# COMPLETE_ArduinoShield_8x8DM.net
KiCad netlist of a schematic drawn in EAGLE
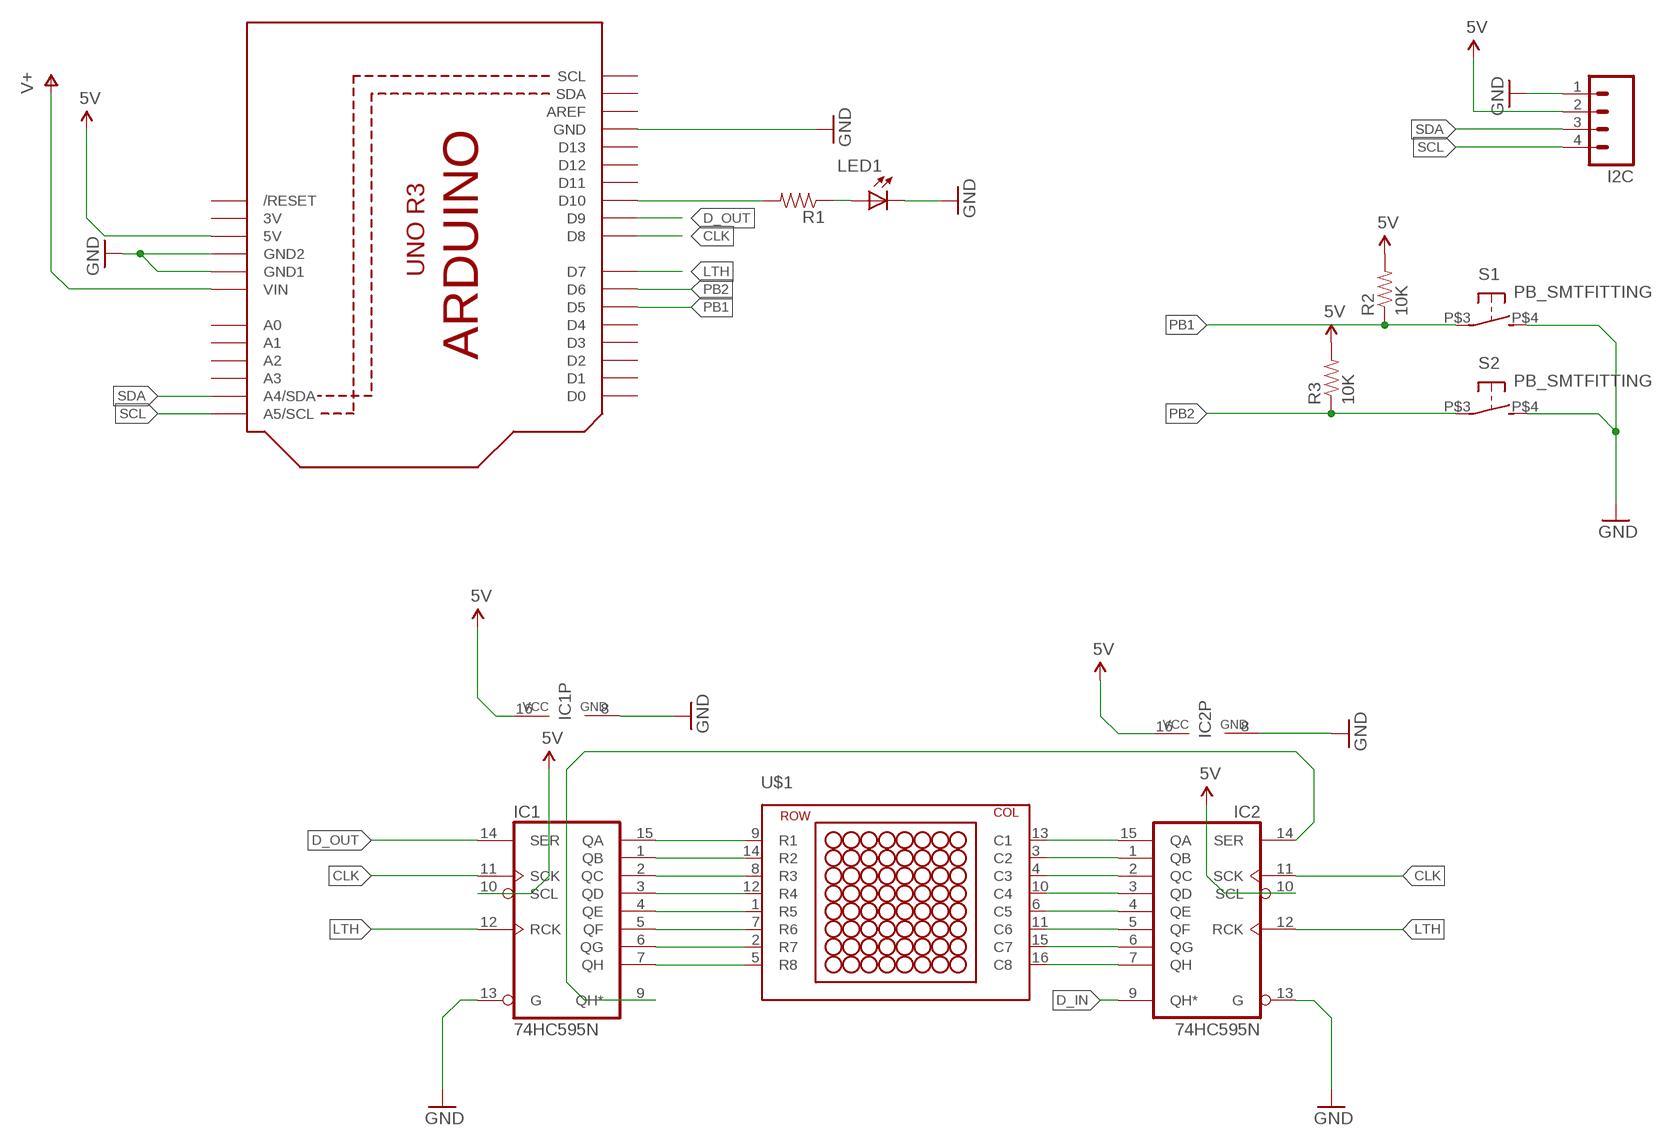
[diagram p0: schematic, sheet 1]

(export (version "E")
  (design (tool "Eeschema 10.0.6"))
  (components
    (comp (ref "I2C")
      (value "M04PTH")
      (footprint "eagle-import:1X04")
      (libsource (lib "eagle-import") (part "M04PTH"))
    )
    (comp (ref "IC1")
      (value "74HC595N")
      (footprint "eagle-import:DIL16")
      (libsource (lib "eagle-import") (part "74595NHC"))
    )
    (comp (ref "IC2")
      (value "74HC595N")
      (footprint "eagle-import:DIL16")
      (libsource (lib "eagle-import") (part "74595NHC"))
    )
    (comp (ref "LED1")
      (value "LED/0805")
      (footprint "eagle-import:CHIP-LED0805")
      (libsource (lib "eagle-import") (part "LED/0805"))
    )
    (comp (ref "R1")
      (value "RESISTOR0805-RES")
      (footprint "eagle-import:0805")
      (libsource (lib "eagle-import") (part "RESISTOR0805-RES"))
    )
    (comp (ref "R2")
      (value "10K")
      (footprint "eagle-import:0805")
      (libsource (lib "eagle-import") (part "RESISTOR0805-RES"))
    )
    (comp (ref "R3")
      (value "10K")
      (footprint "eagle-import:0805")
      (libsource (lib "eagle-import") (part "RESISTOR0805-RES"))
    )
    (comp (ref "S1")
      (value "PB_SMTFITTING")
      (footprint "eagle-import:PB_SMT_TIGHT")
      (libsource (lib "eagle-import") (part "PB_SMTFITTING"))
    )
    (comp (ref "S2")
      (value "PB_SMTFITTING")
      (footprint "eagle-import:PB_SMT_TIGHT")
      (libsource (lib "eagle-import") (part "PB_SMTFITTING"))
    )
    (comp (ref "U$1")
      (value "8X8DM_2088AS")
      (footprint "eagle-import:8X8DM_2088AS")
      (libsource (lib "eagle-import") (part "8X8DM_2088AS"))
    )
    (comp (ref "U1")
      (value "ARDUINOR3-NOIOREF-NOTEXT")
      (footprint "eagle-import:ARDUINOR3-NOTEXT-NOIOREF")
      (libsource (lib "eagle-import") (part "ARDUINOR3-NOIOREF-NOTEXT"))
    )
  )
  (nets
    (net (code "1") (name "/3V") (class "Default")
      (node (ref "U1") (pin "3V") (pinfunction "3V_3V") (pintype "power_in"))
    )
    (net (code "2") (name "5V") (class "Default")
      (node (ref "I2C") (pin "2") (pinfunction "2_2") (pintype "passive"))
      (node (ref "IC1") (pin "10") (pinfunction "SCL_10") (pintype "input"))
      (node (ref "IC1") (pin "16") (pinfunction "VCC_16") (pintype "power_in"))
      (node (ref "IC2") (pin "10") (pinfunction "SCL_10") (pintype "input"))
      (node (ref "IC2") (pin "16") (pinfunction "VCC_16") (pintype "power_in"))
      (node (ref "R2") (pin "2") (pinfunction "2_2") (pintype "passive"))
      (node (ref "R3") (pin "2") (pinfunction "2_2") (pintype "passive"))
      (node (ref "U1") (pin "5V") (pinfunction "5V_5V") (pintype "power_in"))
    )
    (net (code "3") (name "CLK") (class "Default")
      (node (ref "IC1") (pin "11") (pinfunction "SCK_11") (pintype "input"))
      (node (ref "IC2") (pin "11") (pinfunction "SCK_11") (pintype "input"))
      (node (ref "U1") (pin "D8") (pinfunction "D8_D8") (pintype "bidirectional"))
    )
    (net (code "4") (name "D_IN") (class "Default")
      (node (ref "IC2") (pin "9") (pinfunction "QH*_9") (pintype "tri_state"))
    )
    (net (code "5") (name "D_OUT") (class "Default")
      (node (ref "IC1") (pin "14") (pinfunction "SER_14") (pintype "input"))
      (node (ref "U1") (pin "D9") (pinfunction "D9_D9") (pintype "bidirectional"))
    )
    (net (code "6") (name "GND") (class "Default")
      (node (ref "I2C") (pin "1") (pinfunction "1_1") (pintype "passive"))
      (node (ref "IC1") (pin "13") (pinfunction "G_13") (pintype "input"))
      (node (ref "IC1") (pin "8") (pinfunction "GND_8") (pintype "power_in"))
      (node (ref "IC2") (pin "13") (pinfunction "G_13") (pintype "input"))
      (node (ref "IC2") (pin "8") (pinfunction "GND_8") (pintype "power_in"))
      (node (ref "LED1") (pin "C") (pinfunction "C_C") (pintype "passive"))
      (node (ref "S1") (pin "P$4") (pinfunction "2_P$4") (pintype "passive"))
      (node (ref "S2") (pin "P$4") (pinfunction "2_P$4") (pintype "passive"))
      (node (ref "U1") (pin "GND") (pinfunction "GND_GND") (pintype "power_in"))
      (node (ref "U1") (pin "GND1") (pinfunction "GND1_GND1") (pintype "power_in"))
      (node (ref "U1") (pin "GND2") (pinfunction "GND2_GND2") (pintype "power_in"))
    )
    (net (code "7") (name "LTH") (class "Default")
      (node (ref "IC1") (pin "12") (pinfunction "RCK_12") (pintype "input"))
      (node (ref "IC2") (pin "12") (pinfunction "RCK_12") (pintype "input"))
      (node (ref "U1") (pin "D7") (pinfunction "D7_D7") (pintype "bidirectional"))
    )
    (net (code "8") (name "Net-(IC1A-QA)") (class "Default")
      (node (ref "IC1") (pin "15") (pinfunction "QA_15") (pintype "tri_state"))
      (node (ref "U$1") (pin "9") (pinfunction "R1_9") (pintype "bidirectional"))
    )
    (net (code "9") (name "Net-(IC1A-QB)") (class "Default")
      (node (ref "IC1") (pin "1") (pinfunction "QB_1") (pintype "tri_state"))
      (node (ref "U$1") (pin "14") (pinfunction "R2_14") (pintype "bidirectional"))
    )
    (net (code "10") (name "Net-(IC1A-QC)") (class "Default")
      (node (ref "IC1") (pin "2") (pinfunction "QC_2") (pintype "tri_state"))
      (node (ref "U$1") (pin "8") (pinfunction "R3_8") (pintype "bidirectional"))
    )
    (net (code "11") (name "Net-(IC1A-QD)") (class "Default")
      (node (ref "IC1") (pin "3") (pinfunction "QD_3") (pintype "tri_state"))
      (node (ref "U$1") (pin "12") (pinfunction "R4_12") (pintype "bidirectional"))
    )
    (net (code "12") (name "Net-(IC1A-QE)") (class "Default")
      (node (ref "IC1") (pin "4") (pinfunction "QE_4") (pintype "tri_state"))
      (node (ref "U$1") (pin "1") (pinfunction "R5_1") (pintype "bidirectional"))
    )
    (net (code "13") (name "Net-(IC1A-QF)") (class "Default")
      (node (ref "IC1") (pin "5") (pinfunction "QF_5") (pintype "tri_state"))
      (node (ref "U$1") (pin "7") (pinfunction "R6_7") (pintype "bidirectional"))
    )
    (net (code "14") (name "Net-(IC1A-QG)") (class "Default")
      (node (ref "IC1") (pin "6") (pinfunction "QG_6") (pintype "tri_state"))
      (node (ref "U$1") (pin "2") (pinfunction "R7_2") (pintype "bidirectional"))
    )
    (net (code "15") (name "Net-(IC1A-QH)") (class "Default")
      (node (ref "IC1") (pin "7") (pinfunction "QH_7") (pintype "tri_state"))
      (node (ref "U$1") (pin "5") (pinfunction "R8_5") (pintype "bidirectional"))
    )
    (net (code "16") (name "Net-(IC1A-QH*)") (class "Default")
      (node (ref "IC1") (pin "9") (pinfunction "QH*_9") (pintype "tri_state"))
      (node (ref "IC2") (pin "14") (pinfunction "SER_14") (pintype "input"))
    )
    (net (code "17") (name "Net-(IC2A-QA)") (class "Default")
      (node (ref "IC2") (pin "15") (pinfunction "QA_15") (pintype "tri_state"))
      (node (ref "U$1") (pin "13") (pinfunction "C1_13") (pintype "bidirectional"))
    )
    (net (code "18") (name "Net-(IC2A-QB)") (class "Default")
      (node (ref "IC2") (pin "1") (pinfunction "QB_1") (pintype "tri_state"))
      (node (ref "U$1") (pin "3") (pinfunction "C2_3") (pintype "bidirectional"))
    )
    (net (code "19") (name "Net-(IC2A-QC)") (class "Default")
      (node (ref "IC2") (pin "2") (pinfunction "QC_2") (pintype "tri_state"))
      (node (ref "U$1") (pin "4") (pinfunction "C3_4") (pintype "bidirectional"))
    )
    (net (code "20") (name "Net-(IC2A-QD)") (class "Default")
      (node (ref "IC2") (pin "3") (pinfunction "QD_3") (pintype "tri_state"))
      (node (ref "U$1") (pin "10") (pinfunction "C4_10") (pintype "bidirectional"))
    )
    (net (code "21") (name "Net-(IC2A-QE)") (class "Default")
      (node (ref "IC2") (pin "4") (pinfunction "QE_4") (pintype "tri_state"))
      (node (ref "U$1") (pin "6") (pinfunction "C5_6") (pintype "bidirectional"))
    )
    (net (code "22") (name "Net-(IC2A-QF)") (class "Default")
      (node (ref "IC2") (pin "5") (pinfunction "QF_5") (pintype "tri_state"))
      (node (ref "U$1") (pin "11") (pinfunction "C6_11") (pintype "bidirectional"))
    )
    (net (code "23") (name "Net-(IC2A-QG)") (class "Default")
      (node (ref "IC2") (pin "6") (pinfunction "QG_6") (pintype "tri_state"))
      (node (ref "U$1") (pin "15") (pinfunction "C7_15") (pintype "bidirectional"))
    )
    (net (code "24") (name "Net-(IC2A-QH)") (class "Default")
      (node (ref "IC2") (pin "7") (pinfunction "QH_7") (pintype "tri_state"))
      (node (ref "U$1") (pin "16") (pinfunction "C8_16") (pintype "bidirectional"))
    )
    (net (code "25") (name "Net-(LED1-PadA)") (class "Default")
      (node (ref "LED1") (pin "A") (pinfunction "A_A") (pintype "passive"))
      (node (ref "R1") (pin "1") (pinfunction "1_1") (pintype "passive"))
    )
    (net (code "26") (name "Net-(R1-Pad2)") (class "Default")
      (node (ref "R1") (pin "2") (pinfunction "2_2") (pintype "passive"))
      (node (ref "U1") (pin "D10") (pinfunction "D10_D10") (pintype "bidirectional"))
    )
    (net (code "27") (name "PB1") (class "Default")
      (node (ref "R2") (pin "1") (pinfunction "1_1") (pintype "passive"))
      (node (ref "S1") (pin "P$3") (pinfunction "1_P$3") (pintype "passive"))
      (node (ref "U1") (pin "D5") (pinfunction "D5_D5") (pintype "bidirectional"))
    )
    (net (code "28") (name "PB2") (class "Default")
      (node (ref "R3") (pin "1") (pinfunction "1_1") (pintype "passive"))
      (node (ref "S2") (pin "P$3") (pinfunction "1_P$3") (pintype "passive"))
      (node (ref "U1") (pin "D6") (pinfunction "D6_D6") (pintype "bidirectional"))
    )
    (net (code "29") (name "SCL") (class "Default")
      (node (ref "I2C") (pin "4") (pinfunction "4_4") (pintype "passive"))
      (node (ref "U1") (pin "A5") (pinfunction "A5/SCL_A5") (pintype "bidirectional"))
    )
    (net (code "30") (name "SDA") (class "Default")
      (node (ref "I2C") (pin "3") (pinfunction "3_3") (pintype "passive"))
      (node (ref "U1") (pin "A4") (pinfunction "A4/SDA_A4") (pintype "bidirectional"))
    )
    (net (code "31") (name "V+") (class "Default")
      (node (ref "U1") (pin "VIN") (pinfunction "VIN_VIN") (pintype "power_in"))
    )
    (net (code "32") (name "unconnected-(U1-PadA0)") (class "Default")
      (node (ref "U1") (pin "A0") (pinfunction "A0_A0") (pintype "bidirectional"))
    )
    (net (code "33") (name "unconnected-(U1-PadA1)") (class "Default")
      (node (ref "U1") (pin "A1") (pinfunction "A1_A1") (pintype "bidirectional"))
    )
    (net (code "34") (name "unconnected-(U1-PadA2)") (class "Default")
      (node (ref "U1") (pin "A2") (pinfunction "A2_A2") (pintype "bidirectional"))
    )
    (net (code "35") (name "unconnected-(U1-PadA3)") (class "Default")
      (node (ref "U1") (pin "A3") (pinfunction "A3_A3") (pintype "bidirectional"))
    )
    (net (code "36") (name "unconnected-(U1-PadAREF)") (class "Default")
      (node (ref "U1") (pin "AREF") (pinfunction "AREF_AREF") (pintype "bidirectional"))
    )
    (net (code "37") (name "unconnected-(U1-PadD0)") (class "Default")
      (node (ref "U1") (pin "D0") (pinfunction "D0_D0") (pintype "bidirectional"))
    )
    (net (code "38") (name "unconnected-(U1-PadD1)") (class "Default")
      (node (ref "U1") (pin "D1") (pinfunction "D1_D1") (pintype "bidirectional"))
    )
    (net (code "39") (name "unconnected-(U1-PadD2)") (class "Default")
      (node (ref "U1") (pin "D2") (pinfunction "D2_D2") (pintype "bidirectional"))
    )
    (net (code "40") (name "unconnected-(U1-PadD3)") (class "Default")
      (node (ref "U1") (pin "D3") (pinfunction "D3_D3") (pintype "bidirectional"))
    )
    (net (code "41") (name "unconnected-(U1-PadD4)") (class "Default")
      (node (ref "U1") (pin "D4") (pinfunction "D4_D4") (pintype "bidirectional"))
    )
    (net (code "42") (name "unconnected-(U1-PadD11)") (class "Default")
      (node (ref "U1") (pin "D11") (pinfunction "D11_D11") (pintype "bidirectional"))
    )
    (net (code "43") (name "unconnected-(U1-PadD12)") (class "Default")
      (node (ref "U1") (pin "D12") (pinfunction "D12_D12") (pintype "bidirectional"))
    )
    (net (code "44") (name "unconnected-(U1-PadD13)") (class "Default")
      (node (ref "U1") (pin "D13") (pinfunction "D13_D13") (pintype "bidirectional"))
    )
    (net (code "45") (name "unconnected-(U1-PadSCL)") (class "Default")
      (node (ref "U1") (pin "SCL") (pinfunction "SCL_SCL") (pintype "bidirectional"))
    )
    (net (code "46") (name "unconnected-(U1-PadSDA)") (class "Default")
      (node (ref "U1") (pin "SDA") (pinfunction "SDA_SDA") (pintype "bidirectional"))
    )
    (net (code "47") (name "unconnected-(U1-{slash}RESET-PadRESET)") (class "Default")
      (node (ref "U1") (pin "RESET") (pinfunction "/RESET_RESET") (pintype "bidirectional"))
    )
  )
)
